# 02C-001.net
KiCad netlist of a schematic drawn in EAGLE
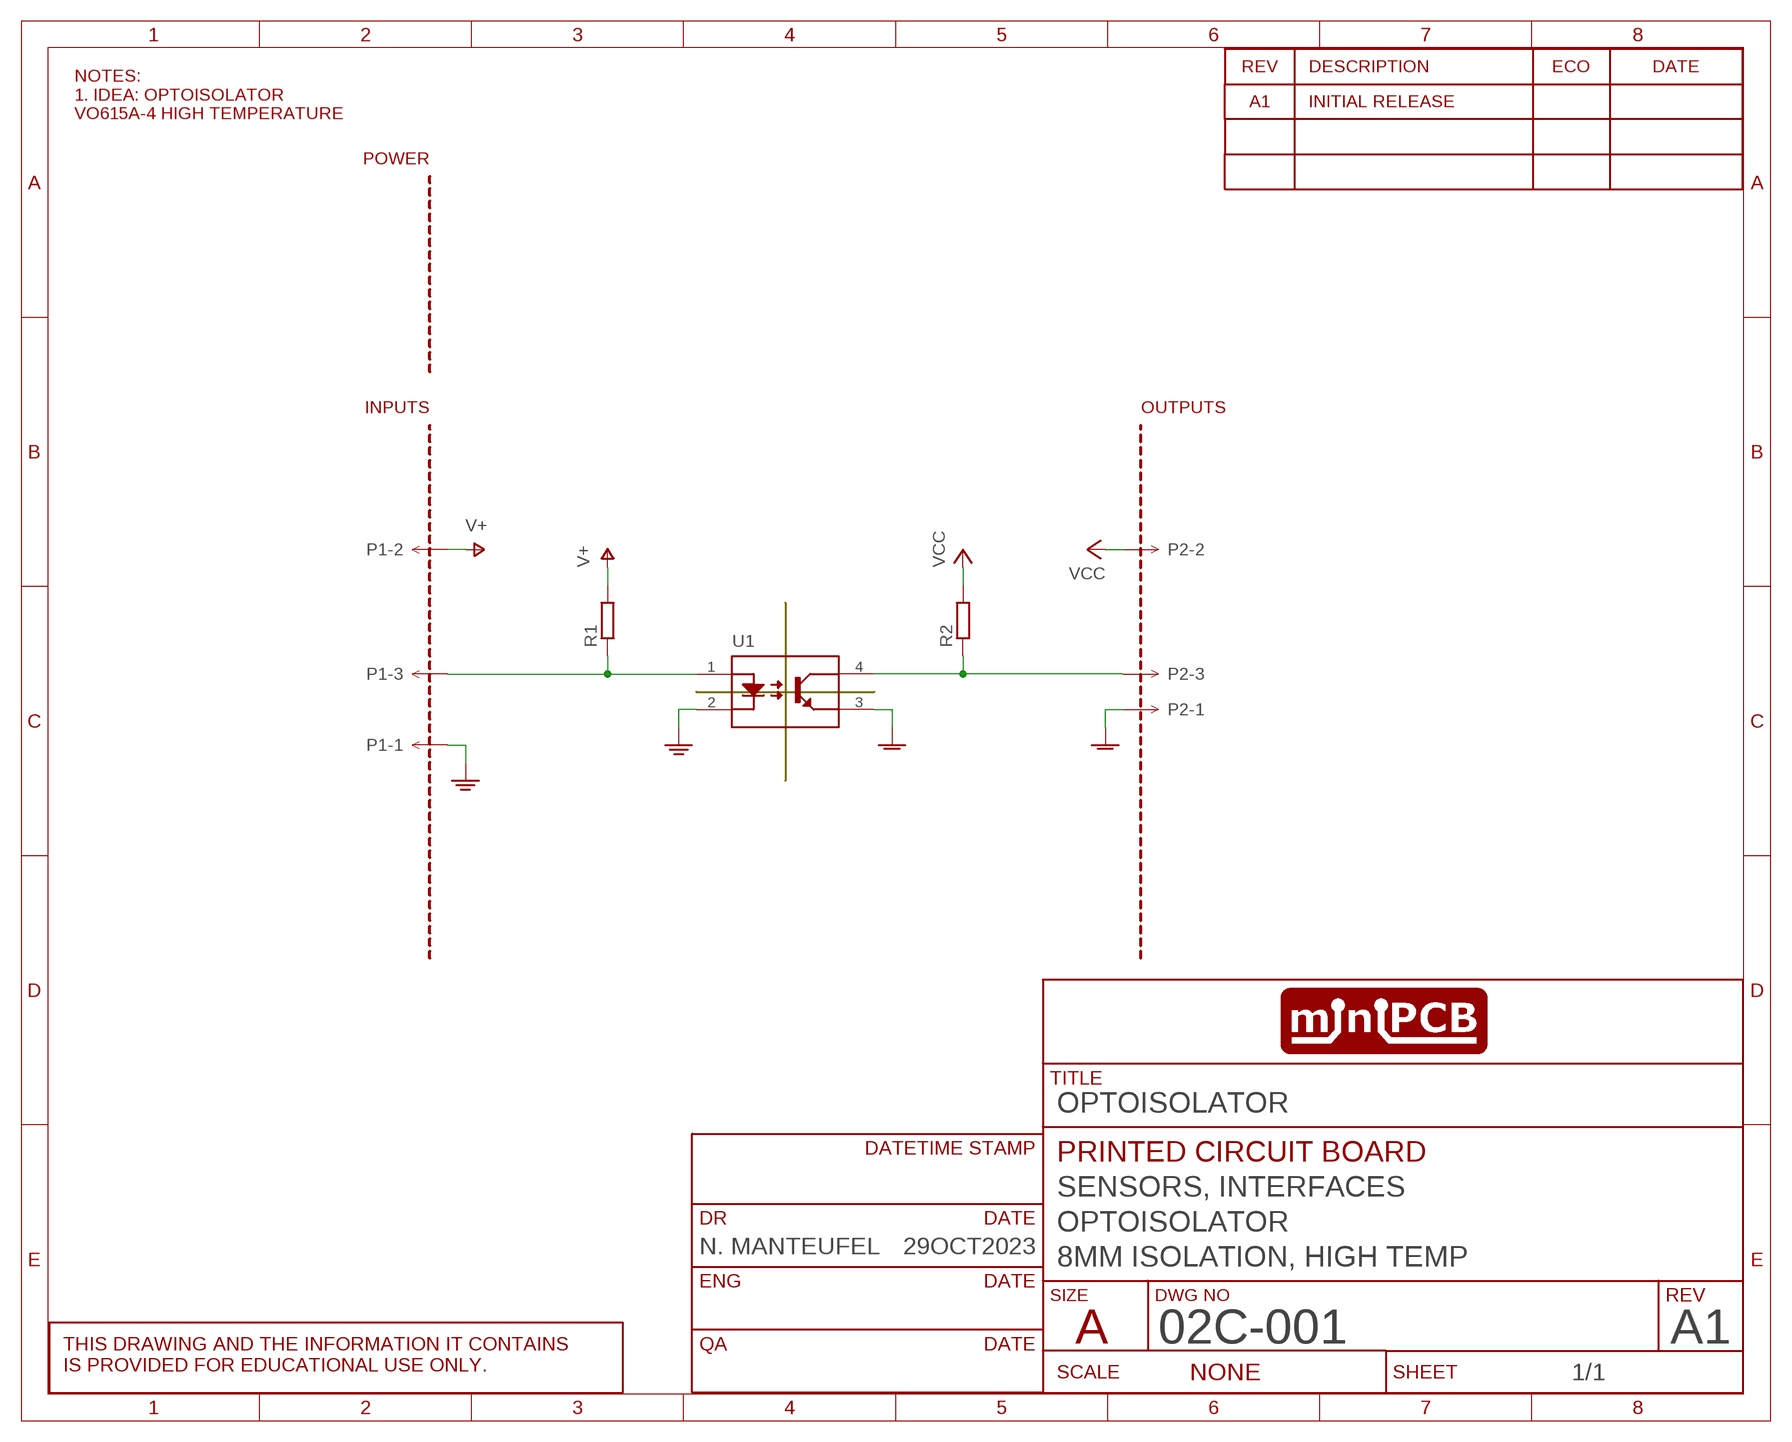
[diagram p0: schematic, sheet 1]

(export (version "E")
  (design (tool "Eeschema 10.0.6"))
  (components
    (comp (ref "P1")
      (value "MINIPCB_3P")
      (footprint "eagle-import:PINS_3")
      (libsource (lib "eagle-import") (part "MINIPCB_3P"))
    )
    (comp (ref "P2")
      (value "MINIPCB_3P")
      (footprint "eagle-import:PINS_3")
      (libsource (lib "eagle-import") (part "MINIPCB_3P"))
    )
    (comp (ref "PCB1")
      (value "MINIPCB_0P00A-20X25")
      (footprint "eagle-import:MINIPCB_00A_20X25")
      (fields (field (name "PART_NUMBER") "02C-001") (field (name "REVISION") "A1-01"))
      (libsource (lib "eagle-import") (part "MINIPCB_0P00A-20X25"))
    )
    (comp (ref "R1")
      (value "RESISTORSMD")
      (footprint "eagle-import:R0805")
      (libsource (lib "eagle-import") (part "RESISTORSMD"))
    )
    (comp (ref "R2")
      (value "RESISTORSMD")
      (footprint "eagle-import:R0805")
      (libsource (lib "eagle-import") (part "RESISTORSMD"))
    )
    (comp (ref "U1")
      (value "OPTOCOUPLER8MM")
      (footprint "eagle-import:OPTOCOUPLE")
      (libsource (lib "eagle-import") (part "OPTOCOUPLER8MM"))
    )
  )
  (nets
    (net (code "1") (name "GND") (class "Default")
      (node (ref "P1") (pin "1") (pinfunction "1_1") (pintype "bidirectional"))
      (node (ref "U1") (pin "2") (pinfunction "2_2") (pintype "bidirectional"))
    )
    (net (code "2") (name "GNDA") (class "Default")
      (node (ref "P2") (pin "1") (pinfunction "1_1") (pintype "bidirectional"))
      (node (ref "U1") (pin "3") (pinfunction "3_3") (pintype "bidirectional"))
    )
    (net (code "3") (name "Net-(P1C-1)") (class "Default")
      (node (ref "P1") (pin "3") (pinfunction "1_3") (pintype "bidirectional"))
      (node (ref "R1") (pin "1") (pinfunction "1_1") (pintype "passive"))
      (node (ref "U1") (pin "1") (pinfunction "1_1") (pintype "bidirectional"))
    )
    (net (code "4") (name "Net-(P2C-1)") (class "Default")
      (node (ref "P2") (pin "3") (pinfunction "1_3") (pintype "bidirectional"))
      (node (ref "R2") (pin "1") (pinfunction "1_1") (pintype "passive"))
      (node (ref "U1") (pin "4") (pinfunction "4_4") (pintype "bidirectional"))
    )
    (net (code "5") (name "V+") (class "Default")
      (node (ref "P1") (pin "2") (pinfunction "1_2") (pintype "bidirectional"))
      (node (ref "R1") (pin "2") (pinfunction "2_2") (pintype "passive"))
    )
    (net (code "6") (name "VCC") (class "Default")
      (node (ref "P2") (pin "2") (pinfunction "1_2") (pintype "bidirectional"))
      (node (ref "R2") (pin "2") (pinfunction "2_2") (pintype "passive"))
    )
  )
)
